# RF_FrontEnd.net
KiCad netlist of a schematic drawn in Altium Designer
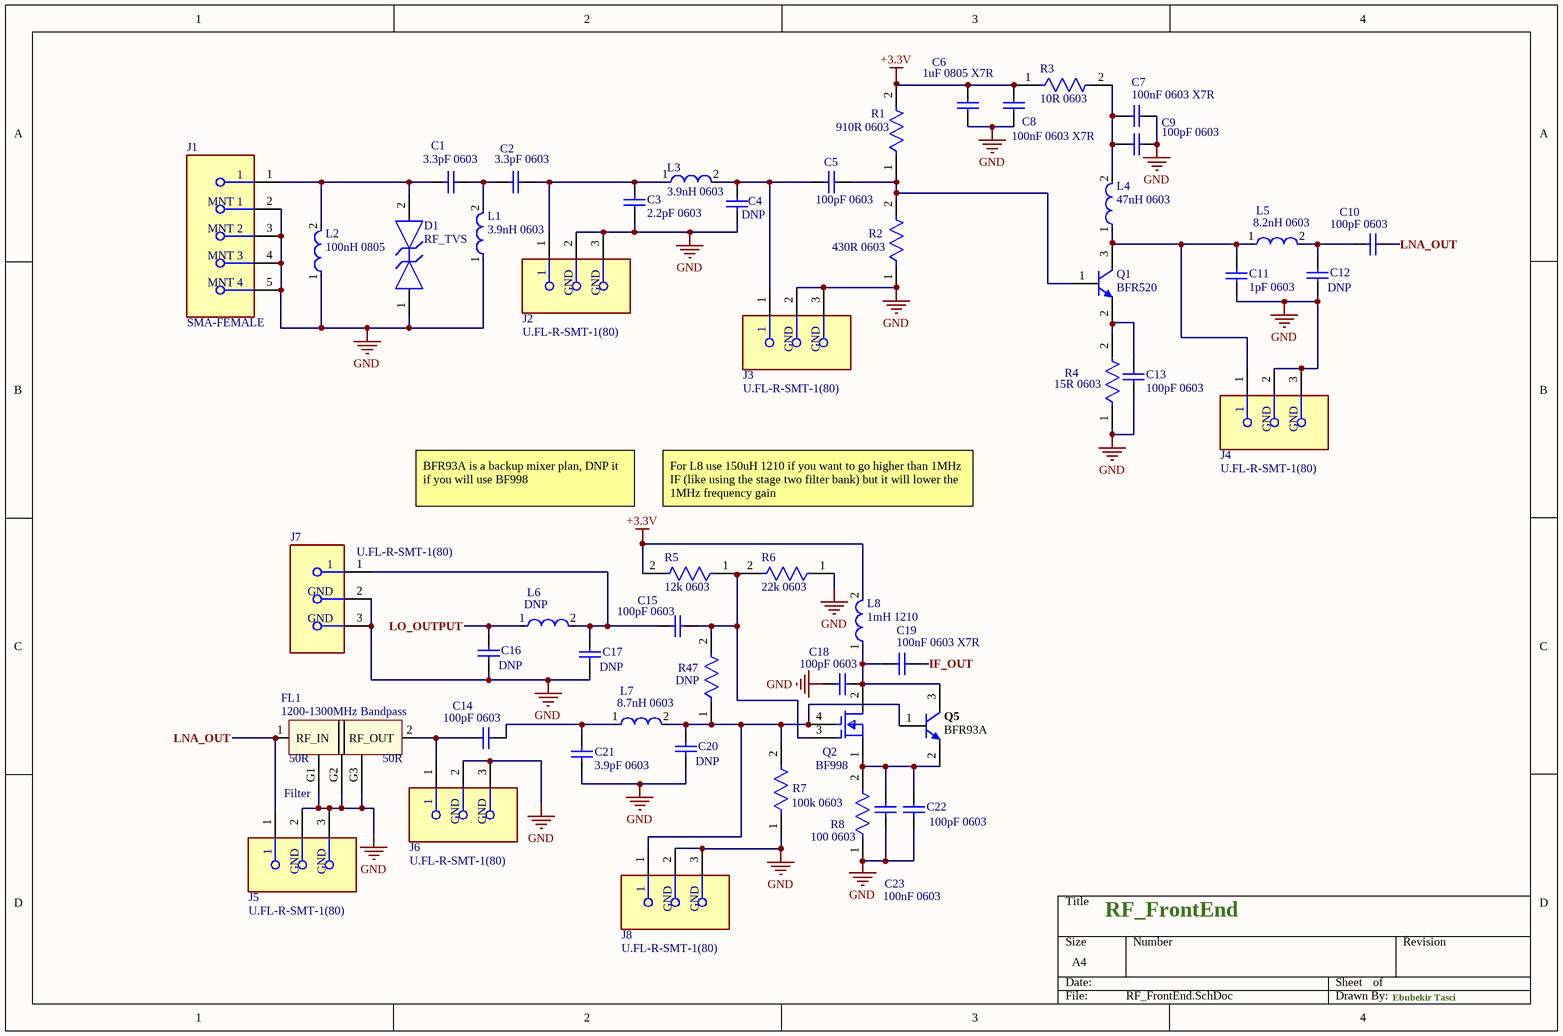
[diagram p0: RF_FrontEnd.SchDoc]

(export (version "E")
  (design (tool "Eeschema 10.0.6"))
  (components
    (comp (ref "C1")
      (value "3.3pF 0603")
      (footprint "CAPC0603(1608)100_L")
      (description "CAP 3.3pF 16V ±0.1pF 0603 (1608 Metric) Thickness 1mm SMD")
      (fields (field (name "TOLERANCE") "Â±0.1pF"))
      (libsource (lib "Altium Content Vault") (part "CAP"))
    )
    (comp (ref "C2")
      (value "3.3pF 0603")
      (footprint "CAPC0603(1608)100_L")
      (description "CAP 3.3pF 16V ±0.1pF 0603 (1608 Metric) Thickness 1mm SMD")
      (fields (field (name "TOLERANCE") "Â±0.1pF"))
      (libsource (lib "Altium Content Vault") (part "CAP"))
    )
    (comp (ref "C3")
      (value "2.2pF 0603")
      (footprint "CAPC0603(1608)100_L")
      (description "CAP 2.2pF 16V ±0.1pF 0603 (1608 Metric) Thickness 1mm SMD")
      (fields (field (name "TOLERANCE") "Â±0.1pF"))
      (libsource (lib "Altium Content Vault") (part "CAP"))
    )
    (comp (ref "C4")
      (value "DNP")
      (footprint "CAPC0603(1608)100_L")
      (description "0603 Extra Pad")
      (libsource (lib "Altium Content Vault") (part "CAP"))
    )
    (comp (ref "C5")
      (value "100pF 0603")
      (footprint "CAPC1608X92X38LL15T08")
      (fields (field (name "MANUFACTURER") "Vitramon") (field (name "PART NUMBER") "VJ0603A101FXAAC"))
      (libsource (lib "Altium Content Vault") (part "CAP"))
    )
    (comp (ref "C6")
      (value "1uF 0805 X7R")
      (footprint "CAPC2013X145X50NL20T20")
      (fields (field (name "PART NUMBER") "VJ0805Y105KXQRW1BC") (field (name "MANUFACTURER") "Vitramon"))
      (libsource (lib "Altium Content Vault") (part "CAP"))
    )
    (comp (ref "C7")
      (value "100nF 0603 X7R")
      (footprint "CAPC1608X92X38NL15T08")
      (fields (field (name "MANUFACTURER") "Vitramon") (field (name "PART NUMBER") "VJ0603Y104KXXAP"))
      (libsource (lib "Altium Content Vault") (part "CAP"))
    )
    (comp (ref "C8")
      (value "100nF 0603 X7R")
      (footprint "CAPC1608X92X38NL15T08")
      (fields (field (name "MANUFACTURER") "Vitramon") (field (name "PART NUMBER") "VJ0603Y104KXXAP"))
      (libsource (lib "Altium Content Vault") (part "CAP"))
    )
    (comp (ref "C9")
      (value "100pF 0603")
      (footprint "CAPC1608X92X38LL15T08")
      (fields (field (name "MANUFACTURER") "Vitramon") (field (name "PART NUMBER") "VJ0603A101FXAAC"))
      (libsource (lib "Altium Content Vault") (part "CAP"))
    )
    (comp (ref "C10")
      (value "100pF 0603")
      (footprint "CAPC1608X92X38LL15T08")
      (fields (field (name "MANUFACTURER") "Vitramon") (field (name "PART NUMBER") "VJ0603A101FXAAC"))
      (libsource (lib "Altium Content Vault") (part "CAP"))
    )
    (comp (ref "C11")
      (value "1pF 0603")
      (footprint "CAPC0603(1608)100_L")
      (description "CAP 1pF 16V ±0.1pF 0603 (1608 Metric) Thickness 1mm SMD")
      (fields (field (name "TOLERANCE") "Â±0.1pF"))
      (libsource (lib "Altium Content Vault") (part "CAP"))
    )
    (comp (ref "C12")
      (value "DNP")
      (footprint "CAPC0603(1608)100_L")
      (description "0603 Extra Pad")
      (libsource (lib "Altium Content Vault") (part "CAP"))
    )
    (comp (ref "C13")
      (value "100pF 0603")
      (footprint "CAPC1608X92X38LL15T08")
      (fields (field (name "MANUFACTURER") "Vitramon") (field (name "PART NUMBER") "VJ0603A101FXAAC"))
      (libsource (lib "Altium Content Vault") (part "CAP"))
    )
    (comp (ref "C14")
      (value "100pF 0603")
      (footprint "CAPC1608X92X38LL15T08")
      (fields (field (name "MANUFACTURER") "Vitramon") (field (name "PART NUMBER") "VJ0603A101FXAAC"))
      (libsource (lib "Altium Content Vault") (part "CAP"))
    )
    (comp (ref "C15")
      (value "100pF 0603")
      (footprint "CAPC1608X92X38LL15T08")
      (fields (field (name "MANUFACTURER") "Vitramon") (field (name "PART NUMBER") "VJ0603A101FXAAC"))
      (libsource (lib "Altium Content Vault") (part "CAP"))
    )
    (comp (ref "C16")
      (value "DNP")
      (footprint "CAPC0603(1608)100_L")
      (description "0603 Extra Pad")
      (libsource (lib "Altium Content Vault") (part "CAP"))
    )
    (comp (ref "C17")
      (value "DNP")
      (footprint "CAPC0603(1608)100_L")
      (description "0603 Extra Pad")
      (libsource (lib "Altium Content Vault") (part "CAP"))
    )
    (comp (ref "C18")
      (value "100pF 0603")
      (footprint "CAPC1608X92X38LL15T08")
      (fields (field (name "MANUFACTURER") "Vitramon") (field (name "PART NUMBER") "VJ0603A101FXAAC"))
      (libsource (lib "Altium Content Vault") (part "CAP"))
    )
    (comp (ref "C19")
      (value "100nF 0603 X7R")
      (footprint "CAPC1608X92X38NL15T08")
      (fields (field (name "MANUFACTURER") "Vitramon") (field (name "PART NUMBER") "VJ0603Y104KXXAP"))
      (libsource (lib "Altium Content Vault") (part "CAP"))
    )
    (comp (ref "C20")
      (value "DNP")
      (footprint "CAPC0603(1608)100_L")
      (description "0603 Extra Pad")
      (libsource (lib "Altium Content Vault") (part "CAP"))
    )
    (comp (ref "C21")
      (value "3.9pF 0603")
      (footprint "CAPC0603(1608)100_L")
      (description "CAP 3.9pF 16V ±0.1pF 0603 (1608 Metric) Thickness 1mm SMD")
      (fields (field (name "TOLERANCE") "Â±0.1pF"))
      (libsource (lib "Altium Content Vault") (part "CAP"))
    )
    (comp (ref "C22")
      (value "100pF 0603")
      (footprint "CAPC1608X92X38LL15T08")
      (fields (field (name "MANUFACTURER") "Vitramon") (field (name "PART NUMBER") "VJ0603A101FXAAC"))
      (libsource (lib "Altium Content Vault") (part "CAP"))
    )
    (comp (ref "C23")
      (value "100nF 0603")
      (footprint "CAPC0603(1608)100_L")
      (description "CAP 100nF 16V ±0.1pF 0603 (1608 Metric) Thickness 1mm SMD")
      (fields (field (name "TOLERANCE") "Â±0.1pF"))
      (libsource (lib "Altium Content Vault") (part "CAP"))
    )
    (comp (ref "D1")
      (value "RF_TVS")
      (footprint "FP-152AF-MFG")
      (description "TVS DIODE 5.3V 14V 2X3DFN\r\nSZESD8472MUT5G")
      (libsource (lib "Altium Content Vault") (part "9a4650ba5e636bd8b2e4c4fb393e9aa"))
    )
    (comp (ref "FL1")
      (value "Filter")
      (footprint "PCBComponent_1")
      (libsource (lib "Filter1") (part "Component_1"))
    )
    (comp (ref "J1")
      (value "SMA-FEMALE")
      (footprint "FP-CON-SMA-EDGE-S-MFG")
      (description "CONN SMA JACK STR EDGE MNT")
      (fields
        (field (name "OCTOPART") "https://octopart.com/con-sma-edge-s-rf+solutions-70967450")
        (field (name "MANUFACTURER PART NUMBER") "CON-SMA-EDGE-S")
      )
      (libsource (lib "Altium Content Vault") (part "a163d97a771fcdd2fd1f1a9264c171f"))
    )
    (comp (ref "J2")
      (value "U.FL-R-SMT-1(80)")
      (footprint "FP-U_FL-R-SMT-1_80-MFG")
      (description "CONN U.FL RCPT STR 50 OHM SMD")
      (libsource (lib "Altium Content Vault") (part "ad010367dc7cd7c7a13299a56582dd6"))
    )
    (comp (ref "J3")
      (value "U.FL-R-SMT-1(80)")
      (footprint "FP-U_FL-R-SMT-1_80-MFG")
      (description "CONN U.FL RCPT STR 50 OHM SMD")
      (libsource (lib "Altium Content Vault") (part "ad010367dc7cd7c7a13299a56582dd6"))
    )
    (comp (ref "J4")
      (value "U.FL-R-SMT-1(80)")
      (footprint "FP-U_FL-R-SMT-1_80-MFG")
      (description "CONN U.FL RCPT STR 50 OHM SMD")
      (libsource (lib "Altium Content Vault") (part "ad010367dc7cd7c7a13299a56582dd6"))
    )
    (comp (ref "J5")
      (value "U.FL-R-SMT-1(80)")
      (footprint "FP-U_FL-R-SMT-1_80-MFG")
      (description "CONN U.FL RCPT STR 50 OHM SMD")
      (libsource (lib "Altium Content Vault") (part "ad010367dc7cd7c7a13299a56582dd6"))
    )
    (comp (ref "J6")
      (value "U.FL-R-SMT-1(80)")
      (footprint "FP-U_FL-R-SMT-1_80-MFG")
      (description "CONN U.FL RCPT STR 50 OHM SMD")
      (libsource (lib "Altium Content Vault") (part "ad010367dc7cd7c7a13299a56582dd6"))
    )
    (comp (ref "J7")
      (value "U.FL-R-SMT-1(80)")
      (footprint "FP-U_FL-R-SMT-1_80-MFG")
      (description "CONN U.FL RCPT STR 50 OHM SMD")
      (libsource (lib "") (part "ad010367dc7cd7c7a13299a56582dd6_1"))
    )
    (comp (ref "J8")
      (value "U.FL-R-SMT-1(80)")
      (footprint "FP-U_FL-R-SMT-1_80-MFG")
      (description "CONN U.FL RCPT STR 50 OHM SMD")
      (libsource (lib "Altium Content Vault") (part "ad010367dc7cd7c7a13299a56582dd6"))
    )
    (comp (ref "L1")
      (value "3.9nH 0603")
      (footprint "FP-AISC-0603HP-MFG")
      (description "FIXED IND 3.9NH SMD")
      (libsource (lib "Altium Content Vault") (part "725321dda6339637d4d059423bc1c3c"))
    )
    (comp (ref "L2")
      (value "100nH 0805")
      (footprint "FP-LQW2BAN_00-MFG")
      (description "Wire Wound RF Inductor 100nH ±2% 400mA 0.46Ω 0805 (2015)")
      (fields (field (name "TOLERANCE") "2%"))
      (libsource (lib "Altium Content Vault") (part "725321dda6339637d4d059423bc1c3c"))
    )
    (comp (ref "L3")
      (value "3.9nH 0603")
      (footprint "FP-AISC-0603HP-MFG")
      (description "FIXED IND 3.9NH SMD")
      (libsource (lib "Altium Content Vault") (part "725321dda6339637d4d059423bc1c3c"))
    )
    (comp (ref "L4")
      (value "47nH 0603")
      (footprint "FP-LQW18AN_80-MFG")
      (description "Wire Wound RF Inductor 47nH ±2% 830mA 0.23Ω 0603 (1608)")
      (fields (field (name "TOLERANCE") "2%"))
      (libsource (lib "Altium Content Vault") (part "725321dda6339637d4d059423bc1c3c"))
    )
    (comp (ref "L5")
      (value "8.2nH 0603")
      (footprint "FP-AISC-0603HP-MFG")
      (description "FIXED IND 8.2NH SMD")
      (fields (field (name "TOLERANCE") "5%"))
      (libsource (lib "Altium Content Vault") (part "725321dda6339637d4d059423bc1c3c"))
    )
    (comp (ref "L6")
      (value "DNP")
      (footprint "FP-AISC-0603HP-MFG")
      (libsource (lib "Altium Content Vault") (part "725321dda6339637d4d059423bc1c3c"))
    )
    (comp (ref "L7")
      (value "8.7nH 0603")
      (footprint "FP-AISC-0603HP-MFG")
      (description "FIXED IND 8.7NH SMD")
      (fields (field (name "TOLERANCE") "5%"))
      (libsource (lib "Altium Content Vault") (part "725321dda6339637d4d059423bc1c3c"))
    )
    (comp (ref "L8")
      (value "1mH 1210")
      (footprint "FP-CB3225-IPC_B")
      (description "SMD Inductors 1000uH ±10% 0.1A 16.9Ω 1210")
      (fields (field (name "TOLERANCE") "10%"))
      (libsource (lib "Altium Content Vault") (part "725321dda6339637d4d059423bc1c3c"))
    )
    (comp (ref "Q1")
      (value "BFR520")
      (footprint "ONSC-SOT-23-3-318-08_V")
      (description "VHF / UHF Transistor, NPN Silicon, 3-Pin SOT-23, Pb-Free, Tape and Reel")
      (libsource (lib "Altium Content Vault") (part "ONSC-NPN-B1E2C3-3"))
    )
    (comp (ref "Q2")
      (value "BF998")
      (footprint "FP-PG-SOT143-4-MFG")
      (description "MOSFET N-CH 12V 200MA SOT-143")
      (libsource (lib "Altium Content Vault") (part "06af6b5b3df8e53fcdd1570485ede4e"))
    )
    (comp (ref "Q5")
      (value "BFR93A")
      (footprint "INF-SOT23_N")
      (description "NPN Silicon RF Transistor, 12 V VCEO, 90 mA IC, 14.5 dB Gmax, SOT23, Green")
      (fields (field (name "MANUFACTURER") "Infineon"))
      (libsource (lib "Altium Content Vault") (part "INF-BFR93A-3"))
    )
    (comp (ref "R1")
      (value "910R 0603")
      (footprint "FP-MCT0603-IPC_A")
      (description "RES SMD 910 OHM 1% 1/8W 0603")
      (fields (field (name "TOLERANCE") "1%"))
      (libsource (lib "Altium Content Vault") (part "1029c3af85768c4190bb7ad29bc67b5"))
    )
    (comp (ref "R2")
      (value "430R 0603")
      (footprint "FP-CPF0603-MFG")
      (description "RES SMD 430Ω 0.1% 1/16W 0603")
      (fields
        (field (name "OCTOPART") "https://octopart.com/cpf0603b430re1-te+connectivity-22738753")
        (field (name "MANUFACTURER PART NUMBER") "CPF0603B430RE1")
      )
      (libsource (lib "Altium Content Vault") (part "1029c3af85768c4190bb7ad29bc67b5"))
    )
    (comp (ref "R3")
      (value "10R 0603")
      (footprint "FP-SR0603-MFG")
      (description "RES SMD 0603 1/4W 1% 10 OHM")
      (fields
        (field (name "MANUFACTURER PART NUMBER") "SR0603FR-7T10RL")
        (field (name "OCTOPART") "https://octopart.com/sr0603fr-7t10rl-yageo-91478074")
      )
      (libsource (lib "Altium Content Vault") (part "1029c3af85768c4190bb7ad29bc67b5"))
    )
    (comp (ref "R4")
      (value "15R 0603")
      (footprint "FP-CPF0603-MFG")
      (description "RES SMD 15Ω 0.1% 1/16W 0603")
      (fields (field (name "TOLERANCE") "0.1%") (field (name "MANUFACTURER") "TE Connectivity"))
      (libsource (lib "Altium Content Vault") (part "1029c3af85768c4190bb7ad29bc67b5"))
    )
    (comp (ref "R5")
      (value "12k 0603")
      (footprint "FP-MCT0603-IPC_A")
      (description "RES SMD 12 KOHM 1% 1/8W 0603")
      (fields (field (name "TOLERANCE") "1%"))
      (libsource (lib "Altium Content Vault") (part "1029c3af85768c4190bb7ad29bc67b5"))
    )
    (comp (ref "R6")
      (value "22k 0603")
      (footprint "FP-MCT0603-IPC_A")
      (description "RES SMD 22 KOHM 1% 1/8W 0603")
      (fields (field (name "TOLERANCE") "1%"))
      (libsource (lib "Altium Content Vault") (part "1029c3af85768c4190bb7ad29bc67b5"))
    )
    (comp (ref "R7")
      (value "100k 0603")
      (footprint "FP-CPF0603-MFG")
      (description "RES SMD 100kΩ 0.1% 1/16W 0603")
      (fields
        (field (name "OCTOPART") "https://octopart.com/cpf0603b430re1-te+connectivity-22738753")
        (field (name "MANUFACTURER PART NUMBER") "CPF0603B430RE1")
      )
      (libsource (lib "Altium Content Vault") (part "1029c3af85768c4190bb7ad29bc67b5"))
    )
    (comp (ref "R8")
      (value "100 0603")
      (footprint "FP-CPF0603-MFG")
      (description "RES SMD 100Ω 0.1% 1/16W 0603")
      (fields
        (field (name "OCTOPART") "https://octopart.com/cpf0603b430re1-te+connectivity-22738753")
        (field (name "MANUFACTURER PART NUMBER") "CPF0603B430RE1")
      )
      (libsource (lib "Altium Content Vault") (part "1029c3af85768c4190bb7ad29bc67b5"))
    )
    (comp (ref "R47")
      (value "DNP")
      (footprint "FP-CPF0603-MFG")
      (description "DNP 0603")
      (fields
        (field (name "OCTOPART") "https://octopart.com/cpf0603b430re1-te+connectivity-22738753")
        (field (name "MANUFACTURER PART NUMBER") "CPF0603B430RE1")
      )
      (libsource (lib "Altium Content Vault") (part "1029c3af85768c4190bb7ad29bc67b5"))
    )
  )
  (nets
    (net (code "1") (name "+3.3V") (class "Default")
      (node (ref "C6") (pin "2") (pinfunction "2_2") (pintype "passive"))
      (node (ref "C8") (pin "2") (pinfunction "2_2") (pintype "passive"))
      (node (ref "L8") (pin "2") (pinfunction "2_2") (pintype "passive"))
      (node (ref "R1") (pin "2") (pinfunction "2_2") (pintype "passive"))
      (node (ref "R3") (pin "1") (pinfunction "1_1") (pintype "passive"))
      (node (ref "R5") (pin "2") (pinfunction "2_2") (pintype "passive"))
    )
    (net (code "2") (name "/IF_OUT") (class "Default")
      (node (ref "C19") (pin "1") (pinfunction "1_1") (pintype "passive"))
    )
    (net (code "3") (name "/LNA_OUT") (class "Default")
      (node (ref "C10") (pin "2") (pinfunction "2_2") (pintype "passive"))
      (node (ref "FL1") (pin "1") (pinfunction "RF_IN_1") (pintype "passive"))
      (node (ref "J5") (pin "1") (pinfunction "1_1") (pintype "passive"))
    )
    (net (code "4") (name "/LO_OUTPUT") (class "Default")
      (node (ref "C16") (pin "2") (pinfunction "2_2") (pintype "passive"))
      (node (ref "L6") (pin "1") (pinfunction "1_1") (pintype "passive"))
    )
    (net (code "5") (name "GND") (class "Default")
      (node (ref "C11") (pin "1") (pinfunction "1_1") (pintype "passive"))
      (node (ref "C12") (pin "1") (pinfunction "1_1") (pintype "passive"))
      (node (ref "C13") (pin "1") (pinfunction "1_1") (pintype "passive"))
      (node (ref "C16") (pin "1") (pinfunction "1_1") (pintype "passive"))
      (node (ref "C17") (pin "1") (pinfunction "1_1") (pintype "passive"))
      (node (ref "C18") (pin "1") (pinfunction "1_1") (pintype "passive"))
      (node (ref "C20") (pin "1") (pinfunction "1_1") (pintype "passive"))
      (node (ref "C21") (pin "1") (pinfunction "1_1") (pintype "passive"))
      (node (ref "C22") (pin "1") (pinfunction "1_1") (pintype "passive"))
      (node (ref "C23") (pin "1") (pinfunction "1_1") (pintype "passive"))
      (node (ref "C3") (pin "1") (pinfunction "1_1") (pintype "passive"))
      (node (ref "C4") (pin "1") (pinfunction "1_1") (pintype "passive"))
      (node (ref "C6") (pin "1") (pinfunction "1_1") (pintype "passive"))
      (node (ref "C7") (pin "1") (pinfunction "1_1") (pintype "passive"))
      (node (ref "C8") (pin "1") (pinfunction "1_1") (pintype "passive"))
      (node (ref "C9") (pin "2") (pinfunction "2_2") (pintype "passive"))
      (node (ref "D1") (pin "1") (pinfunction "1_1") (pintype "passive"))
      (node (ref "FL1") (pin "G1") (pintype "passive"))
      (node (ref "FL1") (pin "G2") (pintype "passive"))
      (node (ref "FL1") (pin "G3") (pintype "passive"))
      (node (ref "J1") (pin "2") (pinfunction "MNT_1_2") (pintype "passive"))
      (node (ref "J1") (pin "3") (pinfunction "MNT_2_3") (pintype "passive"))
      (node (ref "J1") (pin "4") (pinfunction "MNT_3_4") (pintype "passive"))
      (node (ref "J1") (pin "5") (pinfunction "MNT_4_5") (pintype "passive"))
      (node (ref "J2") (pin "2") (pinfunction "GND_2") (pintype "power_in"))
      (node (ref "J2") (pin "3") (pinfunction "GND_3") (pintype "power_in"))
      (node (ref "J3") (pin "2") (pinfunction "GND_2") (pintype "power_in"))
      (node (ref "J3") (pin "3") (pinfunction "GND_3") (pintype "power_in"))
      (node (ref "J4") (pin "2") (pinfunction "GND_2") (pintype "power_in"))
      (node (ref "J4") (pin "3") (pinfunction "GND_3") (pintype "power_in"))
      (node (ref "J5") (pin "2") (pinfunction "GND_2") (pintype "power_in"))
      (node (ref "J5") (pin "3") (pinfunction "GND_3") (pintype "power_in"))
      (node (ref "J6") (pin "2") (pinfunction "GND_2") (pintype "power_in"))
      (node (ref "J6") (pin "3") (pinfunction "GND_3") (pintype "power_in"))
      (node (ref "J7") (pin "2") (pinfunction "GND_2") (pintype "power_in"))
      (node (ref "J7") (pin "3") (pinfunction "GND_3") (pintype "power_in"))
      (node (ref "J8") (pin "2") (pinfunction "GND_2") (pintype "power_in"))
      (node (ref "J8") (pin "3") (pinfunction "GND_3") (pintype "power_in"))
      (node (ref "L1") (pin "1") (pinfunction "1_1") (pintype "passive"))
      (node (ref "L2") (pin "1") (pinfunction "1_1") (pintype "passive"))
      (node (ref "R2") (pin "1") (pinfunction "1_1") (pintype "passive"))
      (node (ref "R4") (pin "1") (pinfunction "1_1") (pintype "passive"))
      (node (ref "R6") (pin "1") (pinfunction "1_1") (pintype "passive"))
      (node (ref "R7") (pin "1") (pinfunction "1_1") (pintype "passive"))
      (node (ref "R8") (pin "1") (pinfunction "1_1") (pintype "passive"))
    )
    (net (code "6") (name "Net-(C1-Pad1)") (class "Default")
      (node (ref "C1") (pin "1") (pinfunction "1_1") (pintype "passive"))
      (node (ref "D1") (pin "2") (pinfunction "2_2") (pintype "passive"))
      (node (ref "J1") (pin "1") (pinfunction "1_1") (pintype "passive"))
      (node (ref "L2") (pin "2") (pinfunction "2_2") (pintype "passive"))
    )
    (net (code "7") (name "Net-(C1-Pad2)") (class "Default")
      (node (ref "C1") (pin "2") (pinfunction "2_2") (pintype "passive"))
      (node (ref "C2") (pin "1") (pinfunction "1_1") (pintype "passive"))
      (node (ref "L1") (pin "2") (pinfunction "2_2") (pintype "passive"))
    )
    (net (code "8") (name "Net-(C2-Pad2)") (class "Default")
      (node (ref "C2") (pin "2") (pinfunction "2_2") (pintype "passive"))
      (node (ref "C3") (pin "2") (pinfunction "2_2") (pintype "passive"))
      (node (ref "J2") (pin "1") (pinfunction "1_1") (pintype "passive"))
      (node (ref "L3") (pin "1") (pinfunction "1_1") (pintype "passive"))
    )
    (net (code "9") (name "Net-(C4-Pad2)") (class "Default")
      (node (ref "C4") (pin "2") (pinfunction "2_2") (pintype "passive"))
      (node (ref "C5") (pin "1") (pinfunction "1_1") (pintype "passive"))
      (node (ref "J3") (pin "1") (pinfunction "1_1") (pintype "passive"))
      (node (ref "L3") (pin "2") (pinfunction "2_2") (pintype "passive"))
    )
    (net (code "10") (name "Net-(C7-Pad2)") (class "Default")
      (node (ref "C7") (pin "2") (pinfunction "2_2") (pintype "passive"))
      (node (ref "C9") (pin "1") (pinfunction "1_1") (pintype "passive"))
      (node (ref "L4") (pin "2") (pinfunction "2_2") (pintype "passive"))
      (node (ref "R3") (pin "2") (pinfunction "2_2") (pintype "passive"))
    )
    (net (code "11") (name "Net-(C10-Pad1)") (class "Default")
      (node (ref "C10") (pin "1") (pinfunction "1_1") (pintype "passive"))
      (node (ref "C12") (pin "2") (pinfunction "2_2") (pintype "passive"))
      (node (ref "L5") (pin "2") (pinfunction "2_2") (pintype "passive"))
    )
    (net (code "12") (name "Net-(C14-Pad2)") (class "Default")
      (node (ref "C14") (pin "2") (pinfunction "2_2") (pintype "passive"))
      (node (ref "C21") (pin "2") (pinfunction "2_2") (pintype "passive"))
      (node (ref "L7") (pin "1") (pinfunction "1_1") (pintype "passive"))
    )
    (net (code "13") (name "Net-(C15-Pad1)") (class "Default")
      (node (ref "C15") (pin "1") (pinfunction "1_1") (pintype "passive"))
      (node (ref "C17") (pin "2") (pinfunction "2_2") (pintype "passive"))
      (node (ref "J7") (pin "1") (pinfunction "1_1") (pintype "passive"))
      (node (ref "L6") (pin "2") (pinfunction "2_2") (pintype "passive"))
    )
    (net (code "14") (name "Net-(FL1-RF_OUT)") (class "Default")
      (node (ref "C14") (pin "1") (pinfunction "1_1") (pintype "passive"))
      (node (ref "FL1") (pin "2") (pinfunction "RF_OUT_2") (pintype "passive"))
      (node (ref "J6") (pin "1") (pinfunction "1_1") (pintype "passive"))
    )
    (net (code "15") (name "Net-(Q1-B)") (class "Default")
      (node (ref "C5") (pin "2") (pinfunction "2_2") (pintype "passive"))
      (node (ref "Q1") (pin "1") (pinfunction "B_1") (pintype "passive"))
      (node (ref "R1") (pin "1") (pinfunction "1_1") (pintype "passive"))
      (node (ref "R2") (pin "2") (pinfunction "2_2") (pintype "passive"))
    )
    (net (code "16") (name "Net-(Q1-C)") (class "Default")
      (node (ref "C11") (pin "2") (pinfunction "2_2") (pintype "passive"))
      (node (ref "J4") (pin "1") (pinfunction "1_1") (pintype "passive"))
      (node (ref "L4") (pin "1") (pinfunction "1_1") (pintype "passive"))
      (node (ref "L5") (pin "1") (pinfunction "1_1") (pintype "passive"))
      (node (ref "Q1") (pin "3") (pinfunction "C_3") (pintype "passive"))
    )
    (net (code "17") (name "Net-(Q1-E)") (class "Default")
      (node (ref "C13") (pin "2") (pinfunction "2_2") (pintype "passive"))
      (node (ref "Q1") (pin "2") (pinfunction "E_2") (pintype "passive"))
      (node (ref "R4") (pin "2") (pinfunction "2_2") (pintype "passive"))
    )
    (net (code "18") (name "Net-(Q2-D)") (class "Default")
      (node (ref "C18") (pin "2") (pinfunction "2_2") (pintype "passive"))
      (node (ref "C19") (pin "2") (pinfunction "2_2") (pintype "passive"))
      (node (ref "L8") (pin "1") (pinfunction "1_1") (pintype "passive"))
      (node (ref "Q2") (pin "2") (pinfunction "D_2") (pintype "passive"))
      (node (ref "Q5") (pin "3") (pinfunction "C_3") (pintype "passive"))
    )
    (net (code "19") (name "Net-(Q2-G1)") (class "Default")
      (node (ref "C20") (pin "2") (pinfunction "2_2") (pintype "passive"))
      (node (ref "J8") (pin "1") (pinfunction "1_1") (pintype "passive"))
      (node (ref "L7") (pin "2") (pinfunction "2_2") (pintype "passive"))
      (node (ref "Q2") (pin "4") (pinfunction "G1_4") (pintype "passive"))
      (node (ref "Q5") (pin "1") (pinfunction "B_1") (pintype "passive"))
      (node (ref "R47") (pin "1") (pinfunction "1_1") (pintype "passive"))
      (node (ref "R7") (pin "2") (pinfunction "2_2") (pintype "passive"))
    )
    (net (code "20") (name "Net-(Q2-G2)") (class "Default")
      (node (ref "C15") (pin "2") (pinfunction "2_2") (pintype "passive"))
      (node (ref "Q2") (pin "3") (pinfunction "G2_3") (pintype "passive"))
      (node (ref "R47") (pin "2") (pinfunction "2_2") (pintype "passive"))
      (node (ref "R5") (pin "1") (pinfunction "1_1") (pintype "passive"))
      (node (ref "R6") (pin "2") (pinfunction "2_2") (pintype "passive"))
    )
    (net (code "21") (name "Net-(Q2-S)") (class "Default")
      (node (ref "C22") (pin "2") (pinfunction "2_2") (pintype "passive"))
      (node (ref "C23") (pin "2") (pinfunction "2_2") (pintype "passive"))
      (node (ref "Q2") (pin "1") (pinfunction "S_1") (pintype "passive"))
      (node (ref "Q5") (pin "2") (pinfunction "E_2") (pintype "passive"))
      (node (ref "R8") (pin "2") (pinfunction "2_2") (pintype "passive"))
    )
  )
)
